# OSSIEPS.net
KiCad netlist of a schematic drawn in EAGLE
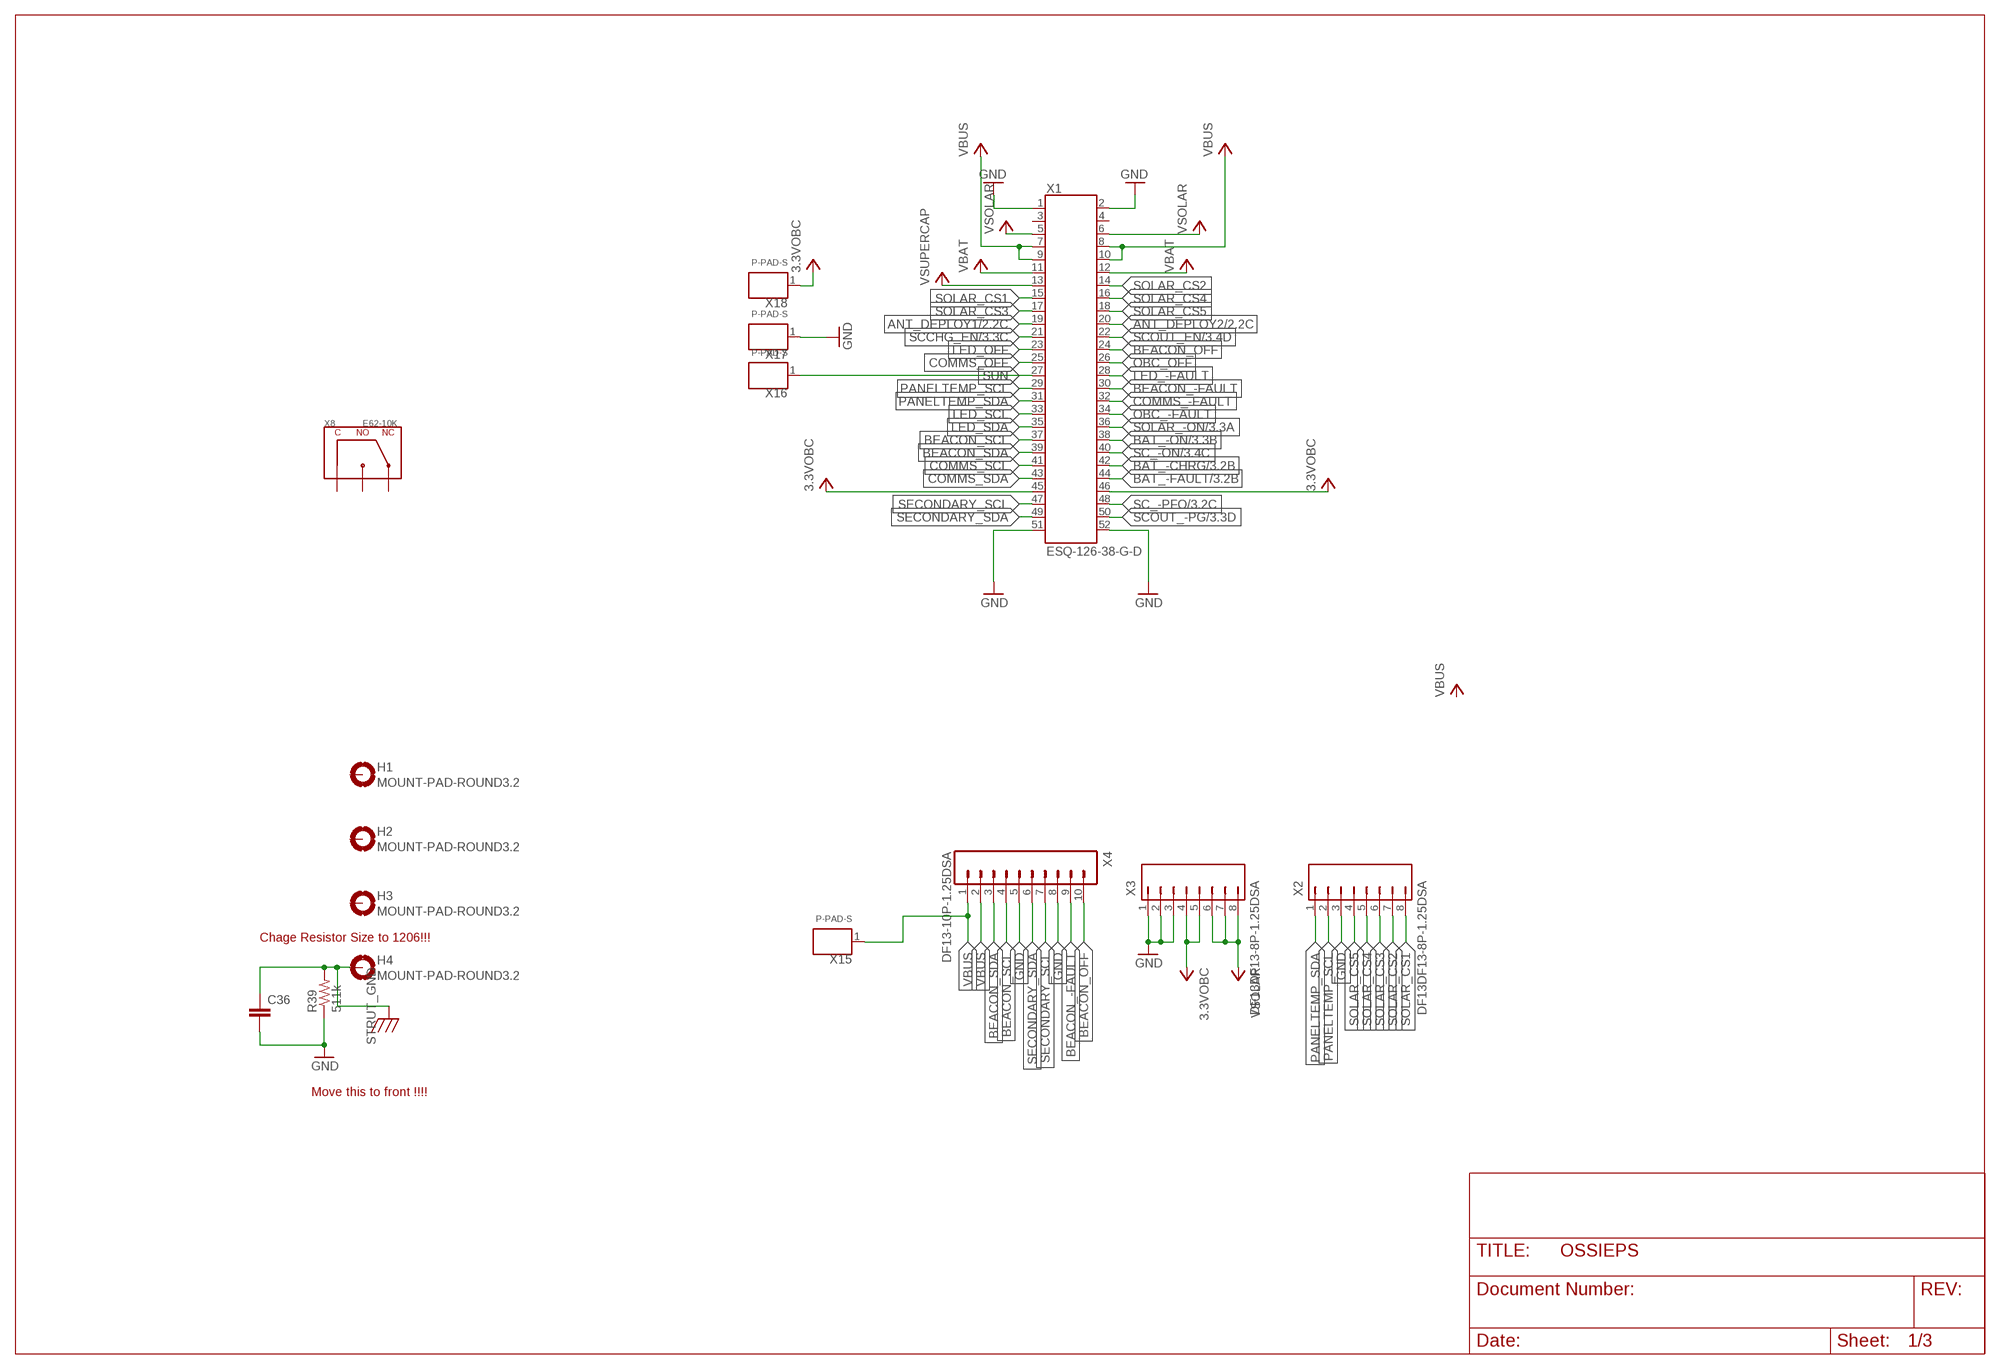
[diagram p0: schematic, sheet 1]
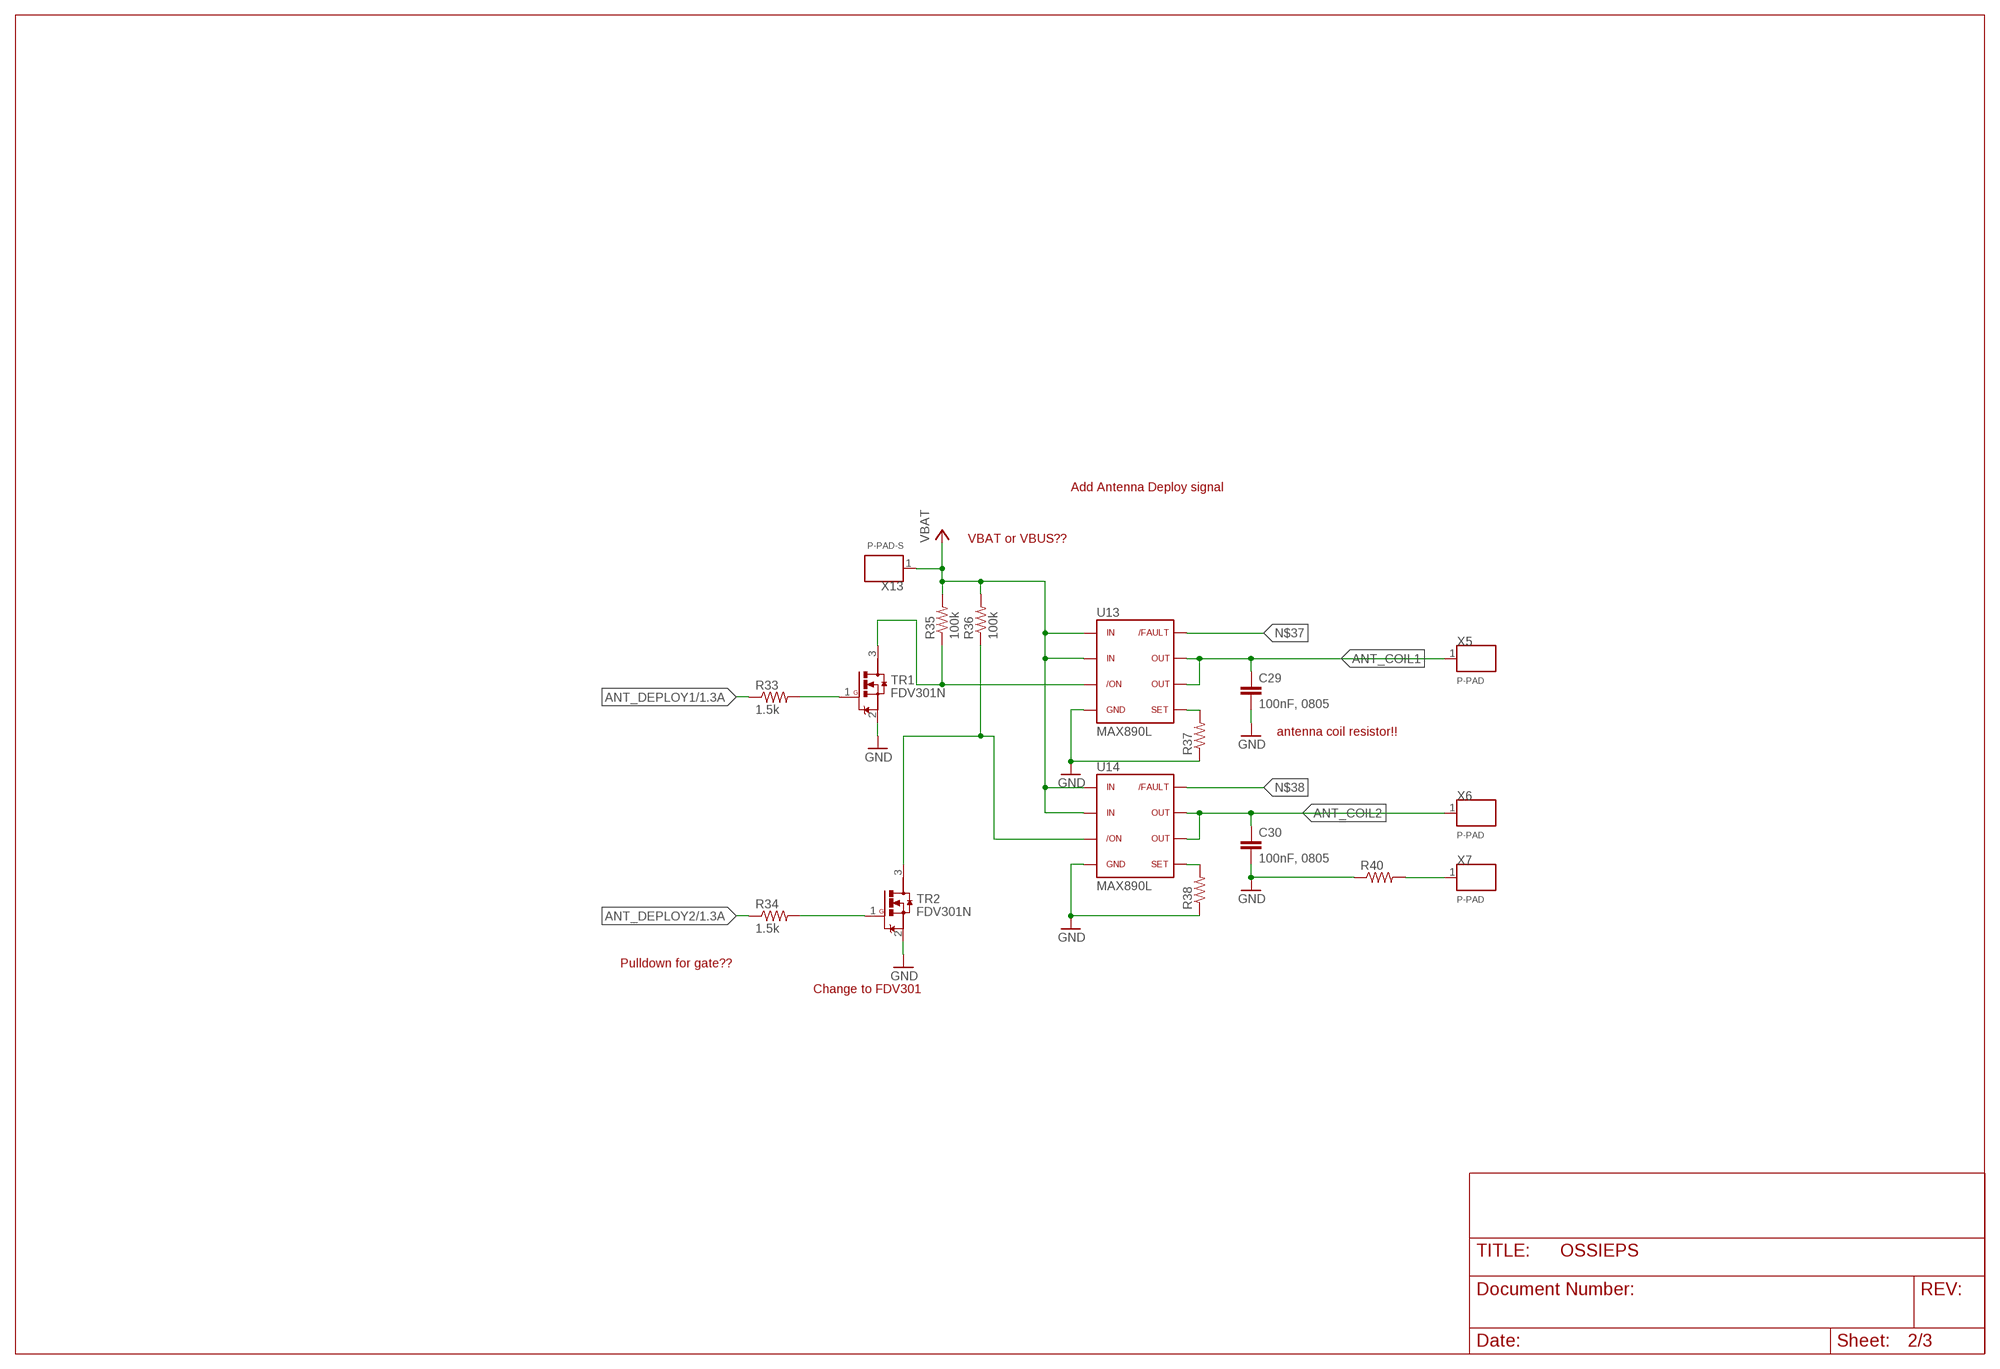
[diagram p1: schematic, sheet 2]
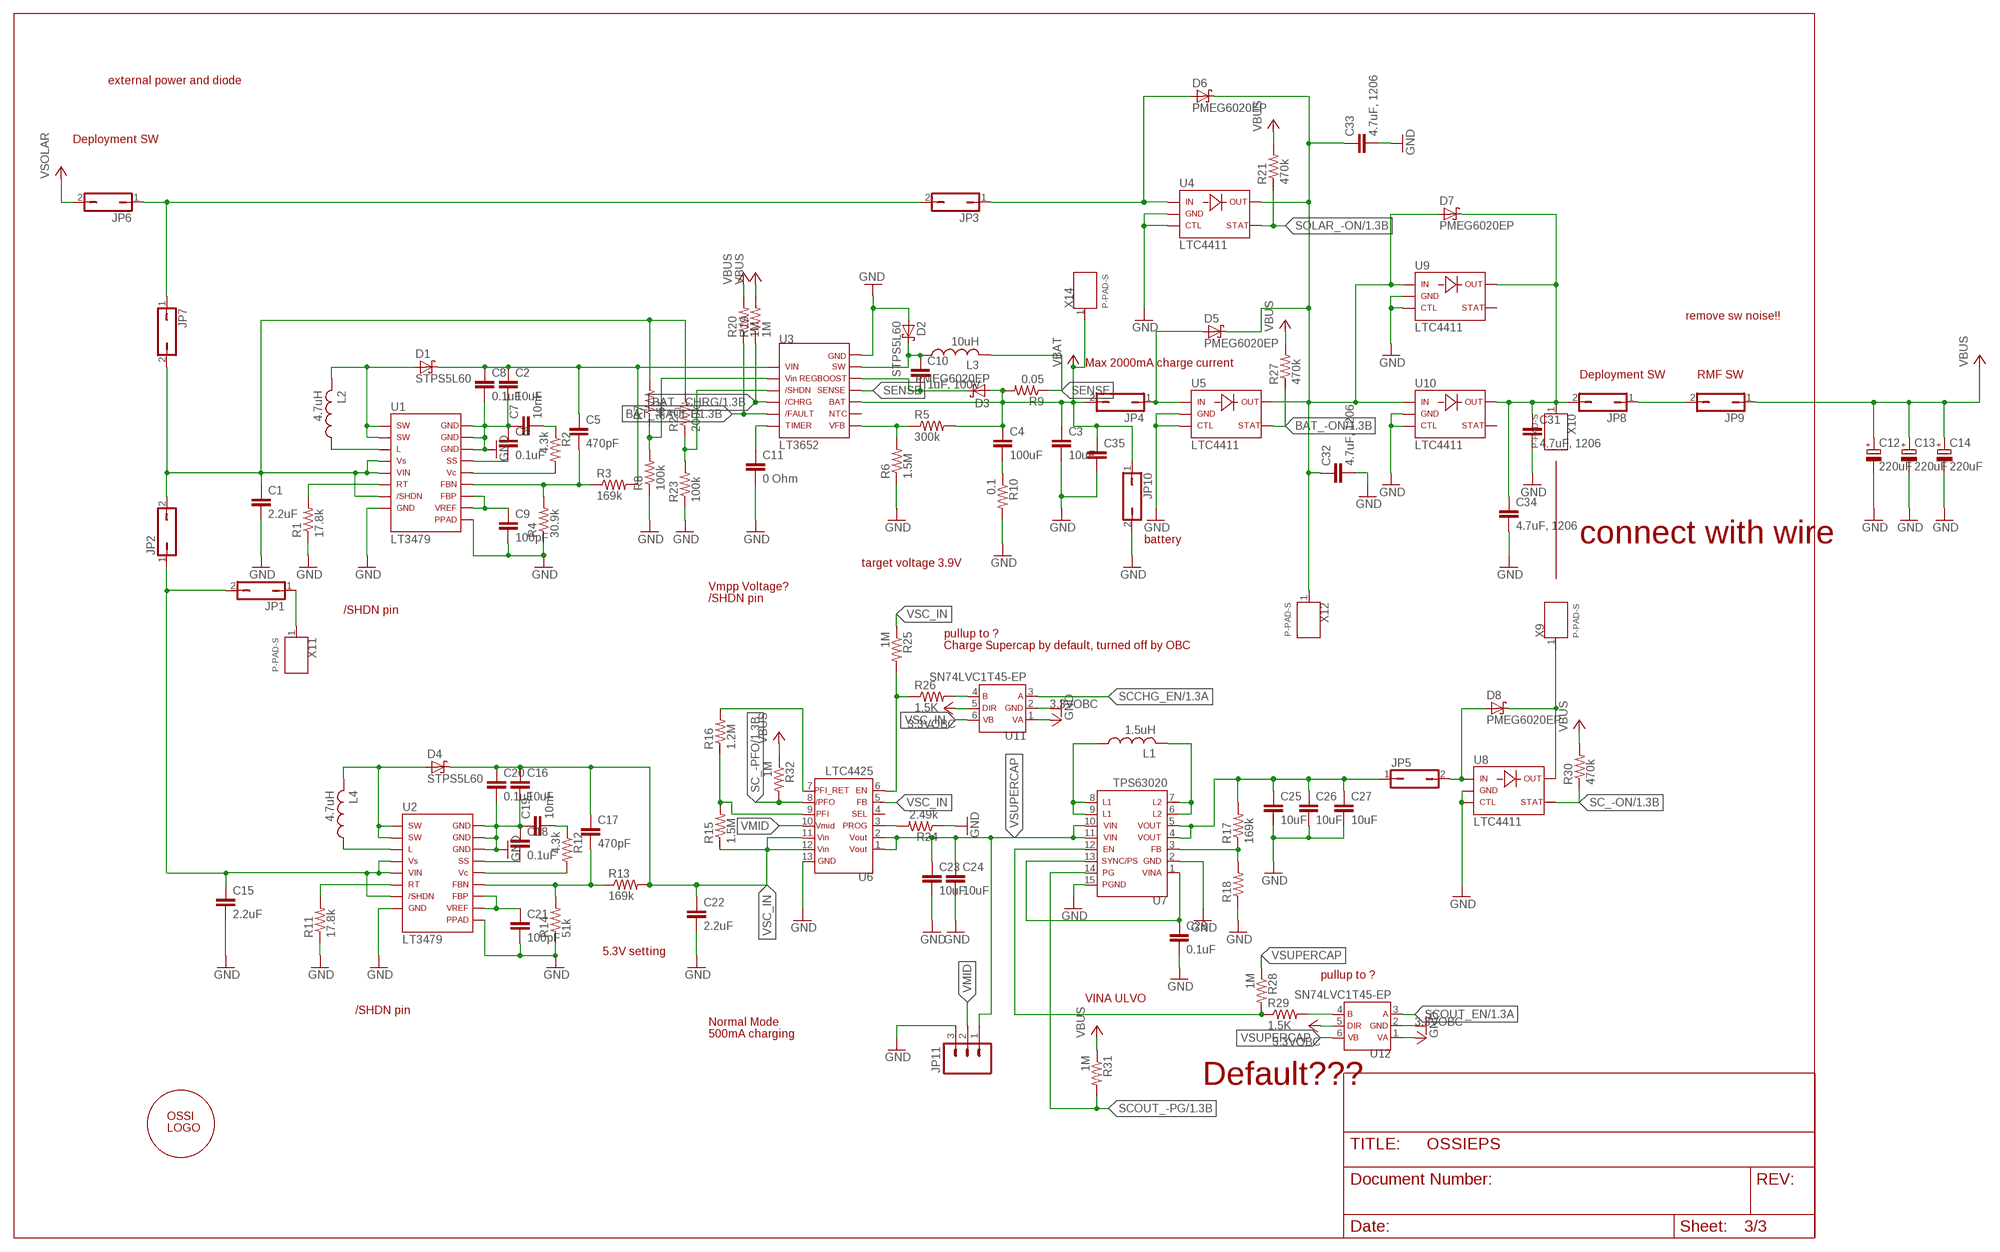
[diagram p2: schematic, sheet 3]

(export (version "E")
  (design (tool "Eeschema 10.0.6"))
  (components
    (comp (ref "C29")
      (value "100nF, 0805")
      (footprint "eagle-import:C0805(2012)")
      (libsource (lib "eagle-import") (part "C0805(2012)"))
    )
    (comp (ref "C30")
      (value "100nF, 0805")
      (footprint "eagle-import:C0805(2012)")
      (libsource (lib "eagle-import") (part "C0805(2012)"))
    )
    (comp (ref "R33")
      (value "1.5k")
      (footprint "eagle-import:R0603(1608)")
      (libsource (lib "eagle-import") (part "R0603(1608)"))
    )
    (comp (ref "R34")
      (value "1.5k")
      (footprint "eagle-import:R0603(1608)")
      (libsource (lib "eagle-import") (part "R0603(1608)"))
    )
    (comp (ref "R35")
      (value "100k")
      (footprint "eagle-import:R0603(1608)")
      (libsource (lib "eagle-import") (part "R0603(1608)"))
    )
    (comp (ref "R36")
      (value "100k")
      (footprint "eagle-import:R0603(1608)")
      (libsource (lib "eagle-import") (part "R0603(1608)"))
    )
    (comp (ref "R37")
      (value "R0603(1608)")
      (footprint "eagle-import:R0603(1608)")
      (libsource (lib "eagle-import") (part "R0603(1608)"))
    )
    (comp (ref "R38")
      (value "R0603(1608)")
      (footprint "eagle-import:R0603(1608)")
      (libsource (lib "eagle-import") (part "R0603(1608)"))
    )
    (comp (ref "R40")
      (value "RPWR263S")
      (footprint "eagle-import:PWR263S-20")
      (libsource (lib "eagle-import") (part "RPWR263S"))
    )
    (comp (ref "TR1")
      (value "FDV301N")
      (footprint "eagle-import:SOT23")
      (libsource (lib "eagle-import") (part "FDV301N"))
    )
    (comp (ref "TR2")
      (value "FDV301N")
      (footprint "eagle-import:SOT23")
      (libsource (lib "eagle-import") (part "FDV301N"))
    )
    (comp (ref "U13")
      (value "MAX890L")
      (footprint "eagle-import:SO8")
      (libsource (lib "eagle-import") (part "MAX890L"))
    )
    (comp (ref "U14")
      (value "MAX890L")
      (footprint "eagle-import:SO8")
      (libsource (lib "eagle-import") (part "MAX890L"))
    )
    (comp (ref "X5")
      (value "P-PAD")
      (footprint "eagle-import:P-PAD")
      (libsource (lib "eagle-import") (part "P-PAD"))
    )
    (comp (ref "X6")
      (value "P-PAD")
      (footprint "eagle-import:P-PAD")
      (libsource (lib "eagle-import") (part "P-PAD"))
    )
    (comp (ref "X7")
      (value "P-PAD")
      (footprint "eagle-import:P-PAD")
      (libsource (lib "eagle-import") (part "P-PAD"))
    )
    (comp (ref "X13")
      (value "P-PAD-S")
      (footprint "eagle-import:P-PAD-S")
      (libsource (lib "eagle-import") (part "P-PAD-S"))
    )
    (comp (ref "C1")
      (value "2.2uF")
      (footprint "eagle-import:C1206-GCM31")
      (libsource (lib "eagle-import") (part "C1206(3216)-GCM31"))
    )
    (comp (ref "C2")
      (value "10uF")
      (footprint "eagle-import:C1210-GCM32")
      (libsource (lib "eagle-import") (part "C1210(3225)-GCM32"))
    )
    (comp (ref "C3")
      (value "10uF")
      (footprint "eagle-import:C1210-GCM32")
      (libsource (lib "eagle-import") (part "C1210(3225)-GCM32"))
    )
    (comp (ref "C4")
      (value "100uF")
      (footprint "eagle-import:C1210-TMK325")
      (libsource (lib "eagle-import") (part "C1210(3225)-TMK325"))
    )
    (comp (ref "C5")
      (value "470pF")
      (footprint "eagle-import:C0603(1608)")
      (libsource (lib "eagle-import") (part "C0603(1608)"))
    )
    (comp (ref "C6")
      (value "0.1uF")
      (footprint "eagle-import:C0603(1608)")
      (libsource (lib "eagle-import") (part "C0603(1608)"))
    )
    (comp (ref "C7")
      (value "10nF")
      (footprint "eagle-import:C0603(1608)")
      (libsource (lib "eagle-import") (part "C0603(1608)"))
    )
    (comp (ref "C8")
      (value "0.1uF")
      (footprint "eagle-import:C0603(1608)")
      (libsource (lib "eagle-import") (part "C0603(1608)"))
    )
    (comp (ref "C9")
      (value "100pF")
      (footprint "eagle-import:C0603(1608)")
      (libsource (lib "eagle-import") (part "C0603(1608)"))
    )
    (comp (ref "C10")
      (value "1uF, 100V")
      (footprint "eagle-import:C0805(2012)")
      (libsource (lib "eagle-import") (part "C0805(2012)"))
    )
    (comp (ref "C11")
      (value "0 Ohm")
      (footprint "eagle-import:C0603(1608)")
      (libsource (lib "eagle-import") (part "C0603(1608)"))
    )
    (comp (ref "C12")
      (value "220uF")
      (footprint "eagle-import:C2917(7343)-Y")
      (libsource (lib "eagle-import") (part "C-TANTAL-Y"))
    )
    (comp (ref "C13")
      (value "220uF")
      (footprint "eagle-import:C2917(7343)-Y")
      (libsource (lib "eagle-import") (part "C-TANTAL-Y"))
    )
    (comp (ref "C14")
      (value "220uF")
      (footprint "eagle-import:C2917(7343)-Y")
      (libsource (lib "eagle-import") (part "C-TANTAL-Y"))
    )
    (comp (ref "C15")
      (value "2.2uF")
      (footprint "eagle-import:C1206-GCM31")
      (libsource (lib "eagle-import") (part "C1206(3216)-GCM31"))
    )
    (comp (ref "C16")
      (value "10uF")
      (footprint "eagle-import:C1210-GCM32")
      (libsource (lib "eagle-import") (part "C1210(3225)-GCM32"))
    )
    (comp (ref "C17")
      (value "470pF")
      (footprint "eagle-import:C0603(1608)")
      (libsource (lib "eagle-import") (part "C0603(1608)"))
    )
    (comp (ref "C18")
      (value "0.1uF")
      (footprint "eagle-import:C0603(1608)")
      (libsource (lib "eagle-import") (part "C0603(1608)"))
    )
    (comp (ref "C19")
      (value "10nF")
      (footprint "eagle-import:C0603(1608)")
      (libsource (lib "eagle-import") (part "C0603(1608)"))
    )
    (comp (ref "C20")
      (value "0.1uF")
      (footprint "eagle-import:C0603(1608)")
      (libsource (lib "eagle-import") (part "C0603(1608)"))
    )
    (comp (ref "C21")
      (value "100pF")
      (footprint "eagle-import:C0603(1608)")
      (libsource (lib "eagle-import") (part "C0603(1608)"))
    )
    (comp (ref "C22")
      (value "2.2uF")
      (footprint "eagle-import:C1206-GCM31")
      (libsource (lib "eagle-import") (part "C1206(3216)-GCM31"))
    )
    (comp (ref "C23")
      (value "10uF")
      (footprint "eagle-import:C1210-GCM32")
      (libsource (lib "eagle-import") (part "C1210(3225)-GCM32"))
    )
    (comp (ref "C24")
      (value "10uF")
      (footprint "eagle-import:C1210-GCM32")
      (libsource (lib "eagle-import") (part "C1210(3225)-GCM32"))
    )
    (comp (ref "C25")
      (value "10uF")
      (footprint "eagle-import:C1210-GCM32")
      (libsource (lib "eagle-import") (part "C1210(3225)-GCM32"))
    )
    (comp (ref "C26")
      (value "10uF")
      (footprint "eagle-import:C1210-GCM32")
      (libsource (lib "eagle-import") (part "C1210(3225)-GCM32"))
    )
    (comp (ref "C27")
      (value "10uF")
      (footprint "eagle-import:C1210-GCM32")
      (libsource (lib "eagle-import") (part "C1210(3225)-GCM32"))
    )
    (comp (ref "C28")
      (value "0.1uF")
      (footprint "eagle-import:C0603(1608)")
      (libsource (lib "eagle-import") (part "C0603(1608)"))
    )
    (comp (ref "C31")
      (value "4.7uF, 1206")
      (footprint "eagle-import:C1206-GCM31")
      (libsource (lib "eagle-import") (part "C1206(3216)-GCM31"))
    )
    (comp (ref "C32")
      (value "4.7uF, 1206")
      (footprint "eagle-import:C1206-GCM31")
      (libsource (lib "eagle-import") (part "C1206(3216)-GCM31"))
    )
    (comp (ref "C33")
      (value "4.7uF, 1206")
      (footprint "eagle-import:C1206-GCM31")
      (libsource (lib "eagle-import") (part "C1206(3216)-GCM31"))
    )
    (comp (ref "C34")
      (value "4.7uF, 1206")
      (footprint "eagle-import:C1206-GCM31")
      (libsource (lib "eagle-import") (part "C1206(3216)-GCM31"))
    )
    (comp (ref "C35")
      (value "C0603(1608)")
      (footprint "eagle-import:C0603(1608)")
      (libsource (lib "eagle-import") (part "C0603(1608)"))
    )
    (comp (ref "D1")
      (value "STPS5L60")
      (footprint "eagle-import:STPS5L60")
      (libsource (lib "eagle-import") (part "STPS5L60"))
    )
    (comp (ref "D2")
      (value "STPS5L60")
      (footprint "eagle-import:STPS5L60")
      (libsource (lib "eagle-import") (part "STPS5L60"))
    )
    (comp (ref "D3")
      (value "PMEG6020EP")
      (footprint "eagle-import:PMEG6020EP")
      (libsource (lib "eagle-import") (part "PMEG6020EP"))
    )
    (comp (ref "D4")
      (value "STPS5L60")
      (footprint "eagle-import:STPS5L60")
      (libsource (lib "eagle-import") (part "STPS5L60"))
    )
    (comp (ref "D5")
      (value "PMEG6020EP")
      (footprint "eagle-import:PMEG6020EP")
      (libsource (lib "eagle-import") (part "PMEG6020EP"))
    )
    (comp (ref "D6")
      (value "PMEG6020EP")
      (footprint "eagle-import:PMEG6020EP")
      (libsource (lib "eagle-import") (part "PMEG6020EP"))
    )
    (comp (ref "D7")
      (value "PMEG6020EP")
      (footprint "eagle-import:PMEG6020EP")
      (libsource (lib "eagle-import") (part "PMEG6020EP"))
    )
    (comp (ref "D8")
      (value "PMEG6020EP")
      (footprint "eagle-import:PMEG6020EP")
      (libsource (lib "eagle-import") (part "PMEG6020EP"))
    )
    (comp (ref "JP1")
      (value "JP1Q")
      (footprint "eagle-import:JP1")
      (libsource (lib "eagle-import") (part "JP1Q"))
    )
    (comp (ref "JP2")
      (value "JP1Q")
      (footprint "eagle-import:JP1")
      (libsource (lib "eagle-import") (part "JP1Q"))
    )
    (comp (ref "JP3")
      (value "JP1Q")
      (footprint "eagle-import:JP1")
      (libsource (lib "eagle-import") (part "JP1Q"))
    )
    (comp (ref "JP4")
      (value "JP1Q")
      (footprint "eagle-import:JP1")
      (libsource (lib "eagle-import") (part "JP1Q"))
    )
    (comp (ref "JP5")
      (value "JP1Q")
      (footprint "eagle-import:JP1")
      (libsource (lib "eagle-import") (part "JP1Q"))
    )
    (comp (ref "JP6")
      (value "JP1Q")
      (footprint "eagle-import:JP1")
      (libsource (lib "eagle-import") (part "JP1Q"))
    )
    (comp (ref "JP7")
      (value "JP1Q")
      (footprint "eagle-import:JP1")
      (libsource (lib "eagle-import") (part "JP1Q"))
    )
    (comp (ref "JP8")
      (value "JP1Q")
      (footprint "eagle-import:JP1")
      (libsource (lib "eagle-import") (part "JP1Q"))
    )
    (comp (ref "JP9")
      (value "JP1Q")
      (footprint "eagle-import:JP1")
      (libsource (lib "eagle-import") (part "JP1Q"))
    )
    (comp (ref "JP10")
      (value "JP1Q")
      (footprint "eagle-import:JP1")
      (libsource (lib "eagle-import") (part "JP1Q"))
    )
    (comp (ref "JP11")
      (value "M03POLAR")
      (footprint "eagle-import:MOLEX-1X3")
      (libsource (lib "eagle-import") (part "M03POLAR"))
    )
    (comp (ref "L1")
      (value "1.5uH")
      (footprint "eagle-import:L(4040)")
      (libsource (lib "eagle-import") (part "LXFL4020"))
    )
    (comp (ref "L2")
      (value "4.7uH")
      (footprint "eagle-import:RLF7030")
      (libsource (lib "eagle-import") (part "LRLF7030"))
    )
    (comp (ref "L3")
      (value "10uH")
      (footprint "eagle-import:RLF12545")
      (libsource (lib "eagle-import") (part "LRLF12545"))
    )
    (comp (ref "L4")
      (value "4.7uH")
      (footprint "eagle-import:RLF7030")
      (libsource (lib "eagle-import") (part "LRLF7030"))
    )
    (comp (ref "R1")
      (value "17.8k")
      (footprint "eagle-import:R0603(1608)")
      (libsource (lib "eagle-import") (part "R0603(1608)"))
    )
    (comp (ref "R2")
      (value "4.3k")
      (footprint "eagle-import:R0603(1608)")
      (libsource (lib "eagle-import") (part "R0603(1608)"))
    )
    (comp (ref "R3")
      (value "169k")
      (footprint "eagle-import:R0603(1608)")
      (libsource (lib "eagle-import") (part "R0603(1608)"))
    )
    (comp (ref "R4")
      (value "30.9k")
      (footprint "eagle-import:R0603(1608)")
      (libsource (lib "eagle-import") (part "R0603(1608)"))
    )
    (comp (ref "R5")
      (value "300k")
      (footprint "eagle-import:R0603(1608)")
      (libsource (lib "eagle-import") (part "R0603(1608)"))
    )
    (comp (ref "R6")
      (value "1.5M")
      (footprint "eagle-import:R0603(1608)")
      (libsource (lib "eagle-import") (part "R0603(1608)"))
    )
    (comp (ref "R7")
      (value "36k")
      (footprint "eagle-import:R0603(1608)")
      (libsource (lib "eagle-import") (part "R0603(1608)"))
    )
    (comp (ref "R8")
      (value "100k")
      (footprint "eagle-import:R0603(1608)")
      (libsource (lib "eagle-import") (part "R0603(1608)"))
    )
    (comp (ref "R9")
      (value "0.05")
      (footprint "eagle-import:WSL1206")
      (libsource (lib "eagle-import") (part "RWSL1206"))
    )
    (comp (ref "R10")
      (value "0.1")
      (footprint "eagle-import:WSL1206")
      (libsource (lib "eagle-import") (part "RWSL1206"))
    )
    (comp (ref "R11")
      (value "17.8k")
      (footprint "eagle-import:R0603(1608)")
      (libsource (lib "eagle-import") (part "R0603(1608)"))
    )
    (comp (ref "R12")
      (value "4.3k")
      (footprint "eagle-import:R0603(1608)")
      (libsource (lib "eagle-import") (part "R0603(1608)"))
    )
    (comp (ref "R13")
      (value "169k")
      (footprint "eagle-import:R0603(1608)")
      (libsource (lib "eagle-import") (part "R0603(1608)"))
    )
    (comp (ref "R14")
      (value "51k")
      (footprint "eagle-import:R0603(1608)")
      (libsource (lib "eagle-import") (part "R0603(1608)"))
    )
    (comp (ref "R15")
      (value "1.5M")
      (footprint "eagle-import:R0603(1608)")
      (libsource (lib "eagle-import") (part "R0603(1608)"))
    )
    (comp (ref "R16")
      (value "1.2M")
      (footprint "eagle-import:R0603(1608)")
      (libsource (lib "eagle-import") (part "R0603(1608)"))
    )
    (comp (ref "R17")
      (value "169k")
      (footprint "eagle-import:R0603(1608)")
      (libsource (lib "eagle-import") (part "R0603(1608)"))
    )
    (comp (ref "R18")
      (value "R0603(1608)")
      (footprint "eagle-import:R0603(1608)")
      (libsource (lib "eagle-import") (part "R0603(1608)"))
    )
    (comp (ref "R19")
      (value "1M")
      (footprint "eagle-import:R0603(1608)")
      (libsource (lib "eagle-import") (part "R0603(1608)"))
    )
    (comp (ref "R20")
      (value "1M")
      (footprint "eagle-import:R0603(1608)")
      (libsource (lib "eagle-import") (part "R0603(1608)"))
    )
    (comp (ref "R21")
      (value "470k")
      (footprint "eagle-import:R0603(1608)")
      (libsource (lib "eagle-import") (part "R0603(1608)"))
    )
    (comp (ref "R22")
      (value "200k")
      (footprint "eagle-import:R0603(1608)")
      (libsource (lib "eagle-import") (part "R0603(1608)"))
    )
    (comp (ref "R23")
      (value "100k")
      (footprint "eagle-import:R0603(1608)")
      (libsource (lib "eagle-import") (part "R0603(1608)"))
    )
    (comp (ref "R24")
      (value "2.49k")
      (footprint "eagle-import:R0603(1608)")
      (libsource (lib "eagle-import") (part "R0603(1608)"))
    )
    (comp (ref "R25")
      (value "1M")
      (footprint "eagle-import:R0603(1608)")
      (libsource (lib "eagle-import") (part "R0603(1608)"))
    )
    (comp (ref "R26")
      (value "1.5K")
      (footprint "eagle-import:R0603(1608)")
      (libsource (lib "eagle-import") (part "R0603(1608)"))
    )
    (comp (ref "R27")
      (value "470k")
      (footprint "eagle-import:R0603(1608)")
      (libsource (lib "eagle-import") (part "R0603(1608)"))
    )
    (comp (ref "R28")
      (value "1M")
      (footprint "eagle-import:R0603(1608)")
      (libsource (lib "eagle-import") (part "R0603(1608)"))
    )
    (comp (ref "R29")
      (value "1.5K")
      (footprint "eagle-import:R0603(1608)")
      (libsource (lib "eagle-import") (part "R0603(1608)"))
    )
    (comp (ref "R30")
      (value "470k")
      (footprint "eagle-import:R0603(1608)")
      (libsource (lib "eagle-import") (part "R0603(1608)"))
    )
    (comp (ref "R31")
      (value "1M")
      (footprint "eagle-import:R0603(1608)")
      (libsource (lib "eagle-import") (part "R0603(1608)"))
    )
    (comp (ref "R32")
      (value "1M")
      (footprint "eagle-import:R0603(1608)")
      (libsource (lib "eagle-import") (part "R0603(1608)"))
    )
    (comp (ref "U$1")
      (value "OSSILOGORECT")
      (footprint "eagle-import:OSSILOGORECT1005")
      (libsource (lib "eagle-import") (part "OSSILOGORECT"))
    )
    (comp (ref "U1")
      (value "LT3479")
      (footprint "eagle-import:TSSOP16-FE")
      (libsource (lib "eagle-import") (part "LT3479"))
    )
    (comp (ref "U2")
      (value "LT3479")
      (footprint "eagle-import:TSSOP16-FE")
      (libsource (lib "eagle-import") (part "LT3479"))
    )
    (comp (ref "U3")
      (value "LT3652")
      (footprint "eagle-import:MSE")
      (libsource (lib "eagle-import") (part "LT3652"))
    )
    (comp (ref "U4")
      (value "LTC4411")
      (footprint "eagle-import:TSOT23-5")
      (libsource (lib "eagle-import") (part "LTC4411"))
    )
    (comp (ref "U5")
      (value "LTC4411")
      (footprint "eagle-import:TSOT23-5")
      (libsource (lib "eagle-import") (part "LTC4411"))
    )
    (comp (ref "U6")
      (value "LTC4425")
      (footprint "eagle-import:MSE")
      (libsource (lib "eagle-import") (part "LTC4425"))
    )
    (comp (ref "U7")
      (value "TPS63020")
      (footprint "eagle-import:VSON-14")
      (libsource (lib "eagle-import") (part "TPS63020"))
    )
    (comp (ref "U8")
      (value "LTC4411")
      (footprint "eagle-import:TSOT23-5")
      (libsource (lib "eagle-import") (part "LTC4411"))
    )
    (comp (ref "U9")
      (value "LTC4411")
      (footprint "eagle-import:TSOT23-5")
      (libsource (lib "eagle-import") (part "LTC4411"))
    )
    (comp (ref "U10")
      (value "LTC4411")
      (footprint "eagle-import:TSOT23-5")
      (libsource (lib "eagle-import") (part "LTC4411"))
    )
    (comp (ref "U11")
      (value "SN74LVC1T45-EP")
      (footprint "eagle-import:SOT-6DCK")
      (libsource (lib "eagle-import") (part "SN74LVC1T45-EP"))
    )
    (comp (ref "U12")
      (value "SN74LVC1T45-EP")
      (footprint "eagle-import:SOT-6DCK")
      (libsource (lib "eagle-import") (part "SN74LVC1T45-EP"))
    )
    (comp (ref "X9")
      (value "P-PAD-S")
      (footprint "eagle-import:P-PAD-S")
      (libsource (lib "eagle-import") (part "P-PAD-S"))
    )
    (comp (ref "X10")
      (value "P-PAD-S")
      (footprint "eagle-import:P-PAD-S")
      (libsource (lib "eagle-import") (part "P-PAD-S"))
    )
    (comp (ref "X11")
      (value "P-PAD-S")
      (footprint "eagle-import:P-PAD-S")
      (libsource (lib "eagle-import") (part "P-PAD-S"))
    )
    (comp (ref "X12")
      (value "P-PAD-S")
      (footprint "eagle-import:P-PAD-S")
      (libsource (lib "eagle-import") (part "P-PAD-S"))
    )
    (comp (ref "X14")
      (value "P-PAD-S")
      (footprint "eagle-import:P-PAD-S")
      (libsource (lib "eagle-import") (part "P-PAD-S"))
    )
    (comp (ref "C36")
      (value "C0805(2012)")
      (footprint "eagle-import:C0805(2012)")
      (libsource (lib "eagle-import") (part "C0805(2012)"))
    )
    (comp (ref "H1")
      (value "MOUNT-PAD-ROUND3.2")
      (footprint "eagle-import:3.2-PAD-ROUND")
      (libsource (lib "eagle-import") (part "MOUNT-PAD-ROUND3.2"))
    )
    (comp (ref "H2")
      (value "MOUNT-PAD-ROUND3.2")
      (footprint "eagle-import:3.2-PAD-ROUND")
      (libsource (lib "eagle-import") (part "MOUNT-PAD-ROUND3.2"))
    )
    (comp (ref "H3")
      (value "MOUNT-PAD-ROUND3.2")
      (footprint "eagle-import:3.2-PAD-ROUND")
      (libsource (lib "eagle-import") (part "MOUNT-PAD-ROUND3.2"))
    )
    (comp (ref "H4")
      (value "MOUNT-PAD-ROUND3.2")
      (footprint "eagle-import:3.2-PAD-ROUND")
      (libsource (lib "eagle-import") (part "MOUNT-PAD-ROUND3.2"))
    )
    (comp (ref "R39")
      (value "511k")
      (footprint "eagle-import:R0805(2012)")
      (libsource (lib "eagle-import") (part "R0805(2012)"))
    )
    (comp (ref "X1")
      (value "ESQ-126-38-G-D")
      (footprint "eagle-import:ESQ-126-XX-X-D")
      (libsource (lib "eagle-import") (part "ESQ-126-38-G-D"))
    )
    (comp (ref "X2")
      (value "DF13DF13-8P-1.25DSA")
      (footprint "eagle-import:DF13-8P-1.25DSA")
      (libsource (lib "eagle-import") (part "DF13DF13-8P-1.25DSA"))
    )
    (comp (ref "X3")
      (value "DF13DF13-8P-1.25DSA")
      (footprint "eagle-import:DF13-8P-1.25DSA")
      (libsource (lib "eagle-import") (part "DF13DF13-8P-1.25DSA"))
    )
    (comp (ref "X4")
      (value "DF13-10P-1.25DSA")
      (footprint "eagle-import:DF13-10P-1.25DSA")
      (libsource (lib "eagle-import") (part "DF13-10P-1.25DSA"))
    )
    (comp (ref "X8")
      (value "E62-10K")
      (footprint "eagle-import:E62-10K")
      (libsource (lib "eagle-import") (part "E62-10K"))
    )
    (comp (ref "X15")
      (value "P-PAD-S")
      (footprint "eagle-import:P-PAD-S")
      (libsource (lib "eagle-import") (part "P-PAD-S"))
    )
    (comp (ref "X16")
      (value "P-PAD-S")
      (footprint "eagle-import:P-PAD-S")
      (libsource (lib "eagle-import") (part "P-PAD-S"))
    )
    (comp (ref "X17")
      (value "P-PAD-S")
      (footprint "eagle-import:P-PAD-S")
      (libsource (lib "eagle-import") (part "P-PAD-S"))
    )
    (comp (ref "X18")
      (value "P-PAD-S")
      (footprint "eagle-import:P-PAD-S")
      (libsource (lib "eagle-import") (part "P-PAD-S"))
    )
  )
  (nets
    (net (code "1") (name "3.3VOBC") (class "Default")
      (node (ref "U11") (pin "1") (pinfunction "P$1_1") (pintype "bidirectional"))
      (node (ref "U11") (pin "5") (pinfunction "P$5_5") (pintype "bidirectional"))
      (node (ref "U12") (pin "1") (pinfunction "P$1_1") (pintype "bidirectional"))
      (node (ref "U12") (pin "5") (pinfunction "P$5_5") (pintype "bidirectional"))
      (node (ref "X1") (pin "45") (pinfunction "45_45") (pintype "bidirectional"))
      (node (ref "X1") (pin "46") (pinfunction "46_46") (pintype "bidirectional"))
      (node (ref "X18") (pin "1") (pinfunction "P$1_1") (pintype "bidirectional"))
      (node (ref "X3") (pin "4") (pinfunction "4_4") (pintype "passive"))
      (node (ref "X3") (pin "5") (pinfunction "5_5") (pintype "passive"))
    )
    (net (code "2") (name "ANT_COIL1") (class "Default")
      (node (ref "C29") (pin "1") (pinfunction "1_1") (pintype "passive"))
      (node (ref "U13") (pin "6") (pinfunction "P$6_6") (pintype "output"))
      (node (ref "U13") (pin "7") (pinfunction "P$7_7") (pintype "output"))
      (node (ref "X5") (pin "1") (pinfunction "P$1_1") (pintype "bidirectional"))
    )
    (net (code "3") (name "ANT_COIL2") (class "Default")
      (node (ref "C30") (pin "1") (pinfunction "1_1") (pintype "passive"))
      (node (ref "U14") (pin "6") (pinfunction "P$6_6") (pintype "output"))
      (node (ref "U14") (pin "7") (pinfunction "P$7_7") (pintype "output"))
      (node (ref "X6") (pin "1") (pinfunction "P$1_1") (pintype "bidirectional"))
    )
    (net (code "4") (name "ANT_DEPLOY1") (class "Default")
      (node (ref "R33") (pin "1") (pinfunction "1_1") (pintype "passive"))
      (node (ref "X1") (pin "19") (pinfunction "19_19") (pintype "bidirectional"))
    )
    (net (code "5") (name "ANT_DEPLOY2") (class "Default")
      (node (ref "R34") (pin "1") (pinfunction "1_1") (pintype "passive"))
      (node (ref "X1") (pin "20") (pinfunction "20_20") (pintype "bidirectional"))
    )
    (net (code "6") (name "BAT_-CHRG") (class "Default")
      (node (ref "R19") (pin "1") (pinfunction "1_1") (pintype "passive"))
      (node (ref "U3") (pin "4") (pinfunction "P$4_4") (pintype "output"))
      (node (ref "X1") (pin "42") (pinfunction "42_42") (pintype "bidirectional"))
    )
    (net (code "7") (name "BAT_-FAULT") (class "Default")
      (node (ref "R20") (pin "1") (pinfunction "1_1") (pintype "passive"))
      (node (ref "U3") (pin "5") (pinfunction "P$5_5") (pintype "output"))
      (node (ref "X1") (pin "44") (pinfunction "44_44") (pintype "bidirectional"))
    )
    (net (code "8") (name "BAT_-ON") (class "Default")
      (node (ref "R27") (pin "1") (pinfunction "1_1") (pintype "passive"))
      (node (ref "U5") (pin "P$4") (pinfunction "P$4_P$4") (pintype "output"))
      (node (ref "X1") (pin "38") (pinfunction "38_38") (pintype "bidirectional"))
    )
    (net (code "9") (name "BEACON_-FAULT") (class "Default")
      (node (ref "X1") (pin "30") (pinfunction "30_30") (pintype "bidirectional"))
      (node (ref "X4") (pin "9") (pinfunction "9_9") (pintype "passive"))
    )
    (net (code "10") (name "BEACON_OFF") (class "Default")
      (node (ref "X1") (pin "24") (pinfunction "24_24") (pintype "bidirectional"))
      (node (ref "X4") (pin "10") (pinfunction "10_10") (pintype "passive"))
    )
    (net (code "11") (name "BEACON_SCL") (class "Default")
      (node (ref "X1") (pin "37") (pinfunction "37_37") (pintype "bidirectional"))
      (node (ref "X4") (pin "4") (pinfunction "4_4") (pintype "passive"))
    )
    (net (code "12") (name "BEACON_SDA") (class "Default")
      (node (ref "X1") (pin "39") (pinfunction "39_39") (pintype "bidirectional"))
      (node (ref "X4") (pin "3") (pinfunction "3_3") (pintype "passive"))
    )
    (net (code "13") (name "COMMS_-FAULT") (class "Default")
      (node (ref "X1") (pin "32") (pinfunction "32_32") (pintype "bidirectional"))
    )
    (net (code "14") (name "COMMS_OFF") (class "Default")
      (node (ref "X1") (pin "25") (pinfunction "25_25") (pintype "bidirectional"))
    )
    (net (code "15") (name "COMMS_SCL") (class "Default")
      (node (ref "X1") (pin "41") (pinfunction "41_41") (pintype "bidirectional"))
    )
    (net (code "16") (name "COMMS_SDA") (class "Default")
      (node (ref "X1") (pin "43") (pinfunction "43_43") (pintype "bidirectional"))
    )
    (net (code "17") (name "GND") (class "Default")
      (node (ref "C1") (pin "P$2") (pinfunction "2_P$2") (pintype "passive"))
      (node (ref "C11") (pin "2") (pinfunction "2_2") (pintype "passive"))
      (node (ref "C12") (pin "2") (pinfunction "-_2") (pintype "passive"))
      (node (ref "C13") (pin "2") (pinfunction "-_2") (pintype "passive"))
      (node (ref "C14") (pin "2") (pinfunction "-_2") (pintype "passive"))
      (node (ref "C15") (pin "P$2") (pinfunction "2_P$2") (pintype "passive"))
      (node (ref "C16") (pin "P$2") (pinfunction "2_P$2") (pintype "passive"))
      (node (ref "C18") (pin "1") (pinfunction "1_1") (pintype "passive"))
      (node (ref "C19") (pin "1") (pinfunction "1_1") (pintype "passive"))
      (node (ref "C2") (pin "P$2") (pinfunction "2_P$2") (pintype "passive"))
      (node (ref "C20") (pin "2") (pinfunction "2_2") (pintype "passive"))
      (node (ref "C21") (pin "2") (pinfunction "2_2") (pintype "passive"))
      (node (ref "C22") (pin "P$2") (pinfunction "2_P$2") (pintype "passive"))
      (node (ref "C23") (pin "P$2") (pinfunction "2_P$2") (pintype "passive"))
      (node (ref "C24") (pin "P$2") (pinfunction "2_P$2") (pintype "passive"))
      (node (ref "C25") (pin "P$2") (pinfunction "2_P$2") (pintype "passive"))
      (node (ref "C26") (pin "P$2") (pinfunction "2_P$2") (pintype "passive"))
      (node (ref "C27") (pin "P$2") (pinfunction "2_P$2") (pintype "passive"))
      (node (ref "C28") (pin "2") (pinfunction "2_2") (pintype "passive"))
      (node (ref "C29") (pin "2") (pinfunction "2_2") (pintype "passive"))
      (node (ref "C3") (pin "P$2") (pinfunction "2_P$2") (pintype "passive"))
      (node (ref "C30") (pin "2") (pinfunction "2_2") (pintype "passive"))
      (node (ref "C31") (pin "P$2") (pinfunction "2_P$2") (pintype "passive"))
      (node (ref "C32") (pin "P$2") (pinfunction "2_P$2") (pintype "passive"))
      (node (ref "C33") (pin "P$2") (pinfunction "2_P$2") (pintype "passive"))
      (node (ref "C34") (pin "P$2") (pinfunction "2_P$2") (pintype "passive"))
      (node (ref "C35") (pin "2") (pinfunction "2_2") (pintype "passive"))
      (node (ref "C36") (pin "2") (pinfunction "2_2") (pintype "passive"))
      (node (ref "C6") (pin "1") (pinfunction "1_1") (pintype "passive"))
      (node (ref "C7") (pin "1") (pinfunction "1_1") (pintype "passive"))
      (node (ref "C8") (pin "2") (pinfunction "2_2") (pintype "passive"))
      (node (ref "C9") (pin "2") (pinfunction "2_2") (pintype "passive"))
      (node (ref "D2") (pin "A") (pinfunction "A_A") (pintype "passive"))
      (node (ref "JP10") (pin "2") (pinfunction "2_2") (pintype "passive"))
      (node (ref "JP11") (pin "3") (pinfunction "3_3") (pintype "passive"))
      (node (ref "R1") (pin "1") (pinfunction "1_1") (pintype "passive"))
      (node (ref "R10") (pin "P$2") (pinfunction "2_P$2") (pintype "passive"))
      (node (ref "R11") (pin "1") (pinfunction "1_1") (pintype "passive"))
      (node (ref "R14") (pin "1") (pinfunction "1_1") (pintype "passive"))
      (node (ref "R18") (pin "1") (pinfunction "1_1") (pintype "passive"))
      (node (ref "R23") (pin "1") (pinfunction "1_1") (pintype "passive"))
      (node (ref "R24") (pin "1") (pinfunction "1_1") (pintype "passive"))
      (node (ref "R37") (pin "1") (pinfunction "1_1") (pintype "passive"))
      (node (ref "R38") (pin "1") (pinfunction "1_1") (pintype "passive"))
      (node (ref "R39") (pin "1") (pinfunction "1_1") (pintype "passive"))
      (node (ref "R4") (pin "1") (pinfunction "1_1") (pintype "passive"))
      (node (ref "R40") (pin "P$1") (pinfunction "1_P$1") (pintype "passive"))
      (node (ref "R6") (pin "1") (pinfunction "1_1") (pintype "passive"))
      (node (ref "R8") (pin "1") (pinfunction "1_1") (pintype "passive"))
      (node (ref "TR1") (pin "2") (pinfunction "S_2") (pintype "bidirectional"))
      (node (ref "TR2") (pin "2") (pinfunction "S_2") (pintype "bidirectional"))
      (node (ref "U1") (pin "14") (pinfunction "P$14_14") (pintype "power_in"))
      (node (ref "U1") (pin "15") (pinfunction "P$15_15") (pintype "power_in"))
      (node (ref "U1") (pin "16") (pinfunction "P$16_16") (pintype "power_in"))
      (node (ref "U1") (pin "8") (pinfunction "P$8_8") (pintype "power_in"))
      (node (ref "U1") (pin "PPAD") (pinfunction "P$17_PPAD") (pintype "power_in"))
      (node (ref "U10") (pin "P$2") (pinfunction "P$2_P$2") (pintype "power_in"))
      (node (ref "U10") (pin "P$3") (pinfunction "P$3_P$3") (pintype "input"))
      (node (ref "U11") (pin "2") (pinfunction "P$2_2") (pintype "bidirectional"))
      (node (ref "U12") (pin "2") (pinfunction "P$2_2") (pintype "bidirectional"))
      (node (ref "U13") (pin "4") (pinfunction "P$4_4") (pintype "power_in"))
      (node (ref "U14") (pin "4") (pinfunction "P$4_4") (pintype "power_in"))
      (node (ref "U2") (pin "14") (pinfunction "P$14_14") (pintype "power_in"))
      (node (ref "U2") (pin "15") (pinfunction "P$15_15") (pintype "power_in"))
      (node (ref "U2") (pin "16") (pinfunction "P$16_16") (pintype "power_in"))
      (node (ref "U2") (pin "8") (pinfunction "P$8_8") (pintype "power_in"))
      (node (ref "U2") (pin "PPAD") (pinfunction "P$17_PPAD") (pintype "power_in"))
      (node (ref "U3") (pin "13") (pinfunction "P$13_13") (pintype "bidirectional"))
      (node (ref "U4") (pin "P$2") (pinfunction "P$2_P$2") (pintype "power_in"))
      (node (ref "U4") (pin "P$3") (pinfunction "P$3_P$3") (pintype "input"))
      (node (ref "U5") (pin "P$2") (pinfunction "P$2_P$2") (pintype "power_in"))
      (node (ref "U5") (pin "P$3") (pinfunction "P$3_P$3") (pintype "input"))
      (node (ref "U6") (pin "13") (pinfunction "P$13_13") (pintype "power_in"))
      (node (ref "U7") (pin "15") (pinfunction "PGND_15") (pintype "power_in"))
      (node (ref "U7") (pin "2") (pinfunction "GND_2") (pintype "power_in"))
      (node (ref "U8") (pin "P$2") (pinfunction "P$2_P$2") (pintype "power_in"))
      (node (ref "U8") (pin "P$3") (pinfunction "P$3_P$3") (pintype "input"))
      (node (ref "U9") (pin "P$2") (pinfunction "P$2_P$2") (pintype "power_in"))
      (node (ref "U9") (pin "P$3") (pinfunction "P$3_P$3") (pintype "input"))
      (node (ref "X1") (pin "1") (pinfunction "1_1") (pintype "bidirectional"))
      (node (ref "X1") (pin "2") (pinfunction "2_2") (pintype "bidirectional"))
      (node (ref "X1") (pin "51") (pinfunction "51_51") (pintype "bidirectional"))
      (node (ref "X1") (pin "52") (pinfunction "52_52") (pintype "bidirectional"))
      (node (ref "X17") (pin "1") (pinfunction "P$1_1") (pintype "bidirectional"))
      (node (ref "X2") (pin "3") (pinfunction "3_3") (pintype "passive"))
      (node (ref "X3") (pin "1") (pinfunction "1_1") (pintype "passive"))
      (node (ref "X3") (pin "2") (pinfunction "2_2") (pintype "passive"))
      (node (ref "X3") (pin "3") (pinfunction "3_3") (pintype "passive"))
      (node (ref "X4") (pin "5") (pinfunction "5_5") (pintype "passive"))
      (node (ref "X4") (pin "8") (pinfunction "8_8") (pintype "passive"))
    )
    (net (code "18") (name "LED_-FAULT") (class "Default")
      (node (ref "X1") (pin "28") (pinfunction "28_28") (pintype "bidirectional"))
    )
    (net (code "19") (name "LED_OFF") (class "Default")
      (node (ref "X1") (pin "23") (pinfunction "23_23") (pintype "bidirectional"))
    )
    (net (code "20") (name "LED_SCL") (class "Default")
      (node (ref "X1") (pin "33") (pinfunction "33_33") (pintype "bidirectional"))
    )
    (net (code "21") (name "LED_SDA") (class "Default")
      (node (ref "X1") (pin "35") (pinfunction "35_35") (pintype "bidirectional"))
    )
    (net (code "22") (name "N$37") (class "Default")
      (node (ref "U13") (pin "8") (pinfunction "P$8_8") (pintype "output"))
    )
    (net (code "23") (name "N$38") (class "Default")
      (node (ref "U14") (pin "8") (pinfunction "P$8_8") (pintype "output"))
    )
    (net (code "24") (name "Net-(C1-1)") (class "Default")
      (node (ref "C1") (pin "P$1") (pinfunction "1_P$1") (pintype "passive"))
      (node (ref "JP2") (pin "2") (pinfunction "2_2") (pintype "passive"))
      (node (ref "JP7") (pin "2") (pinfunction "2_2") (pintype "passive"))
      (node (ref "R22") (pin "2") (pinfunction "2_2") (pintype "passive"))
      (node (ref "R7") (pin "2") (pinfunction "2_2") (pintype "passive"))
      (node (ref "U1") (pin "4") (pinfunction "P$4_4") (pintype "power_in"))
      (node (ref "U1") (pin "5") (pinfunction "P$5_5") (pintype "power_in"))
      (node (ref "U1") (pin "7") (pinfunction "P$7_7") (pintype "input"))
    )
    (net (code "25") (name "Net-(C2-1)") (class "Default")
      (node (ref "C2") (pin "P$1") (pinfunction "1_P$1") (pintype "passive"))
      (node (ref "C5") (pin "1") (pinfunction "1_1") (pintype "passive"))
      (node (ref "C8") (pin "1") (pinfunction "1_1") (pintype "passive"))
      (node (ref "D1") (pin "C") (pinfunction "C_C") (pintype "passive"))
      (node (ref "R3") (pin "2") (pinfunction "2_2") (pintype "passive"))
      (node (ref "U3") (pin "1") (pinfunction "P$1_1") (pintype "power_in"))
    )
    (net (code "26") (name "Net-(C4-2)") (class "Default")
      (node (ref "C4") (pin "P$2") (pinfunction "2_P$2") (pintype "passive"))
      (node (ref "R10") (pin "P$1") (pinfunction "1_P$1") (pintype "passive"))
    )
    (net (code "27") (name "Net-(C7-Pad2)") (class "Default")
      (node (ref "C7") (pin "2") (pinfunction "2_2") (pintype "passive"))
      (node (ref "R2") (pin "1") (pinfunction "1_1") (pintype "passive"))
    )
    (net (code "28") (name "Net-(C15-1)") (class "Default")
      (node (ref "C15") (pin "P$1") (pinfunction "1_P$1") (pintype "passive"))
      (node (ref "JP1") (pin "2") (pinfunction "2_2") (pintype "passive"))
      (node (ref "JP2") (pin "1") (pinfunction "1_1") (pintype "passive"))
      (node (ref "U2") (pin "4") (pinfunction "P$4_4") (pintype "power_in"))
      (node (ref "U2") (pin "5") (pinfunction "P$5_5") (pintype "power_in"))
      (node (ref "U2") (pin "7") (pinfunction "P$7_7") (pintype "input"))
    )
    (net (code "29") (name "Net-(C19-Pad2)") (class "Default")
      (node (ref "C19") (pin "2") (pinfunction "2_2") (pintype "passive"))
      (node (ref "R12") (pin "1") (pinfunction "1_1") (pintype "passive"))
    )
    (net (code "30") (name "Net-(C25-1)") (class "Default")
      (node (ref "C25") (pin "P$1") (pinfunction "1_P$1") (pintype "passive"))
      (node (ref "C26") (pin "P$1") (pinfunction "1_P$1") (pintype "passive"))
      (node (ref "C27") (pin "P$1") (pinfunction "1_P$1") (pintype "passive"))
      (node (ref "JP5") (pin "1") (pinfunction "1_1") (pintype "passive"))
      (node (ref "R17") (pin "2") (pinfunction "2_2") (pintype "passive"))
      (node (ref "U7") (pin "4") (pinfunction "VOUT_4") (pintype "output"))
      (node (ref "U7") (pin "5") (pinfunction "VOUT2_5") (pintype "output"))
    )
    (net (code "31") (name "Net-(C31-1)") (class "Default")
      (node (ref "C31") (pin "P$1") (pinfunction "1_P$1") (pintype "passive"))
      (node (ref "C34") (pin "P$1") (pinfunction "1_P$1") (pintype "passive"))
      (node (ref "D7") (pin "C") (pinfunction "C_C") (pintype "passive"))
      (node (ref "JP8") (pin "2") (pinfunction "2_2") (pintype "passive"))
      (node (ref "U10") (pin "P$5") (pinfunction "P$5_P$5") (pintype "power_in"))
      (node (ref "U9") (pin "P$5") (pinfunction "P$5_P$5") (pintype "power_in"))
      (node (ref "X10") (pin "1") (pinfunction "P$1_1") (pintype "bidirectional"))
    )
    (net (code "32") (name "Net-(C32-1)") (class "Default")
      (node (ref "C32") (pin "P$1") (pinfunction "1_P$1") (pintype "passive"))
      (node (ref "C33") (pin "P$1") (pinfunction "1_P$1") (pintype "passive"))
      (node (ref "D5") (pin "C") (pinfunction "C_C") (pintype "passive"))
      (node (ref "D6") (pin "C") (pinfunction "C_C") (pintype "passive"))
      (node (ref "D7") (pin "A") (pinfunction "A_A") (pintype "passive"))
      (node (ref "U10") (pin "P$1") (pinfunction "P$1_P$1") (pintype "input"))
      (node (ref "U4") (pin "P$5") (pinfunction "P$5_P$5") (pintype "power_in"))
      (node (ref "U5") (pin "P$5") (pinfunction "P$5_P$5") (pintype "power_in"))
      (node (ref "U9") (pin "P$1") (pinfunction "P$1_P$1") (pintype "input"))
      (node (ref "X12") (pin "1") (pinfunction "P$1_1") (pintype "bidirectional"))
    )
    (net (code "33") (name "Net-(D5-PadA)") (class "Default")
      (node (ref "D5") (pin "A") (pinfunction "A_A") (pintype "passive"))
      (node (ref "JP4") (pin "1") (pinfunction "1_1") (pintype "passive"))
      (node (ref "U5") (pin "P$1") (pinfunction "P$1_P$1") (pintype "input"))
    )
    (net (code "34") (name "Net-(D6-PadA)") (class "Default")
      (node (ref "D6") (pin "A") (pinfunction "A_A") (pintype "passive"))
      (node (ref "JP3") (pin "1") (pinfunction "1_1") (pintype "passive"))
      (node (ref "U4") (pin "P$1") (pinfunction "P$1_P$1") (pintype "input"))
    )
    (net (code "35") (name "Net-(D8-PadA)") (class "Default")
      (node (ref "D8") (pin "A") (pinfunction "A_A") (pintype "passive"))
      (node (ref "JP5") (pin "2") (pinfunction "2_2") (pintype "passive"))
      (node (ref "U8") (pin "P$1") (pinfunction "P$1_P$1") (pintype "input"))
    )
    (net (code "36") (name "Net-(JP3-Pad2)") (class "Default")
      (node (ref "JP3") (pin "2") (pinfunction "2_2") (pintype "passive"))
      (node (ref "JP6") (pin "1") (pinfunction "1_1") (pintype "passive"))
      (node (ref "JP7") (pin "1") (pinfunction "1_1") (pintype "passive"))
    )
    (net (code "37") (name "Net-(JP8-Pad1)") (class "Default")
      (node (ref "JP8") (pin "1") (pinfunction "1_1") (pintype "passive"))
      (node (ref "JP9") (pin "2") (pinfunction "2_2") (pintype "passive"))
    )
    (net (code "38") (name "Net-(L2-1)") (class "Default")
      (node (ref "L2") (pin "P$1") (pinfunction "1_P$1") (pintype "passive"))
      (node (ref "U1") (pin "3") (pinfunction "P$3_3") (pintype "passive"))
    )
    (net (code "39") (name "Net-(L2-2)") (class "Default")
      (node (ref "D1") (pin "A") (pinfunction "A_A") (pintype "passive"))
      (node (ref "L2") (pin "P$2") (pinfunction "2_P$2") (pintype "passive"))
      (node (ref "U1") (pin "1") (pinfunction "P$1_1") (pintype "power_in"))
      (node (ref "U1") (pin "2") (pinfunction "P$2_2") (pintype "power_in"))
    )
    (net (code "40") (name "Net-(L3-1)") (class "Default")
      (node (ref "C10") (pin "1") (pinfunction "1_1") (pintype "passive"))
      (node (ref "D2") (pin "C") (pinfunction "C_C") (pintype "passive"))
      (node (ref "L3") (pin "P$1") (pinfunction "1_P$1") (pintype "passive"))
      (node (ref "U3") (pin "12") (pinfunction "P$12_12") (pintype "output"))
    )
    (net (code "41") (name "Net-(L4-1)") (class "Default")
      (node (ref "L4") (pin "P$1") (pinfunction "1_P$1") (pintype "passive"))
      (node (ref "U2") (pin "3") (pinfunction "P$3_3") (pintype "passive"))
    )
    (net (code "42") (name "Net-(L4-2)") (class "Default")
      (node (ref "D4") (pin "A") (pinfunction "A_A") (pintype "passive"))
      (node (ref "L4") (pin "P$2") (pinfunction "2_P$2") (pintype "passive"))
      (node (ref "U2") (pin "1") (pinfunction "P$1_1") (pintype "power_in"))
      (node (ref "U2") (pin "2") (pinfunction "P$2_2") (pintype "power_in"))
    )
    (net (code "43") (name "Net-(R40-2)") (class "Default")
      (node (ref "R40") (pin "P$2") (pinfunction "2_P$2") (pintype "passive"))
      (node (ref "X7") (pin "1") (pinfunction "P$1_1") (pintype "bidirectional"))
    )
    (net (code "44") (name "Net-(TR1-D)") (class "Default")
      (node (ref "R35") (pin "1") (pinfunction "1_1") (pintype "passive"))
      (node (ref "TR1") (pin "3") (pinfunction "D_3") (pintype "bidirectional"))
      (node (ref "U13") (pin "3") (pinfunction "P$3_3") (pintype "input"))
    )
    (net (code "45") (name "Net-(TR1-G)") (class "Default")
      (node (ref "R33") (pin "2") (pinfunction "2_2") (pintype "passive"))
      (node (ref "TR1") (pin "1") (pinfunction "G_1") (pintype "bidirectional"))
    )
    (net (code "46") (name "Net-(TR2-D)") (class "Default")
      (node (ref "R36") (pin "1") (pinfunction "1_1") (pintype "passive"))
      (node (ref "TR2") (pin "3") (pinfunction "D_3") (pintype "bidirectional"))
      (node (ref "U14") (pin "3") (pinfunction "P$3_3") (pintype "input"))
    )
    (net (code "47") (name "Net-(TR2-G)") (class "Default")
      (node (ref "R34") (pin "2") (pinfunction "2_2") (pintype "passive"))
      (node (ref "TR2") (pin "1") (pinfunction "G_1") (pintype "bidirectional"))
    )
    (net (code "48") (name "Net-(U1-P$6)") (class "Default")
      (node (ref "R1") (pin "2") (pinfunction "2_2") (pintype "passive"))
      (node (ref "U1") (pin "6") (pinfunction "P$6_6") (pintype "passive"))
    )
    (net (code "49") (name "Net-(U1-P$10)") (class "Default")
      (node (ref "C9") (pin "1") (pinfunction "1_1") (pintype "passive"))
      (node (ref "U1") (pin "10") (pinfunction "P$10_10") (pintype "input"))
      (node (ref "U1") (pin "9") (pinfunction "P$9_9") (pintype "output"))
    )
    (net (code "50") (name "Net-(U1-P$11)") (class "Default")
      (node (ref "C5") (pin "2") (pinfunction "2_2") (pintype "passive"))
      (node (ref "R3") (pin "1") (pinfunction "1_1") (pintype "passive"))
      (node (ref "R4") (pin "2") (pinfunction "2_2") (pintype "passive"))
      (node (ref "U1") (pin "11") (pinfunction "P$11_11") (pintype "input"))
    )
    (net (code "51") (name "Net-(U1-P$12)") (class "Default")
      (node (ref "R2") (pin "2") (pinfunction "2_2") (pintype "passive"))
      (node (ref "U1") (pin "12") (pinfunction "P$12_12") (pintype "input"))
    )
    (net (code "52") (name "Net-(U1-P$13)") (class "Default")
      (node (ref "C6") (pin "2") (pinfunction "2_2") (pintype "passive"))
      (node (ref "U1") (pin "13") (pinfunction "P$13_13") (pintype "input"))
    )
    (net (code "53") (name "Net-(U2-P$6)") (class "Default")
      (node (ref "R11") (pin "2") (pinfunction "2_2") (pintype "passive"))
      (node (ref "U2") (pin "6") (pinfunction "P$6_6") (pintype "passive"))
    )
    (net (code "54") (name "Net-(U2-P$10)") (class "Default")
      (node (ref "C21") (pin "1") (pinfunction "1_1") (pintype "passive"))
      (node (ref "U2") (pin "10") (pinfunction "P$10_10") (pintype "input"))
      (node (ref "U2") (pin "9") (pinfunction "P$9_9") (pintype "output"))
    )
    (net (code "55") (name "Net-(U2-P$11)") (class "Default")
      (node (ref "C17") (pin "2") (pinfunction "2_2") (pintype "passive"))
      (node (ref "R13") (pin "1") (pinfunction "1_1") (pintype "passive"))
      (node (ref "R14") (pin "2") (pinfunction "2_2") (pintype "passive"))
      (node (ref "U2") (pin "11") (pinfunction "P$11_11") (pintype "input"))
    )
    (net (code "56") (name "Net-(U2-P$12)") (class "Default")
      (node (ref "R12") (pin "2") (pinfunction "2_2") (pintype "passive"))
      (node (ref "U2") (pin "12") (pinfunction "P$12_12") (pintype "input"))
    )
    (net (code "57") (name "Net-(U2-P$13)") (class "Default")
      (node (ref "C18") (pin "2") (pinfunction "2_2") (pintype "passive"))
      (node (ref "U2") (pin "13") (pinfunction "P$13_13") (pintype "input"))
    )
    (net (code "58") (name "Net-(U3-P$2)") (class "Default")
      (node (ref "R7") (pin "1") (pinfunction "1_1") (pintype "passive"))
      (node (ref "R8") (pin "2") (pinfunction "2_2") (pintype "passive"))
      (node (ref "U3") (pin "2") (pinfunction "P$2_2") (pintype "input"))
    )
    (net (code "59") (name "Net-(U3-P$3)") (class "Default")
      (node (ref "R22") (pin "1") (pinfunction "1_1") (pintype "passive"))
      (node (ref "R23") (pin "2") (pinfunction "2_2") (pintype "passive"))
      (node (ref "U3") (pin "3") (pinfunction "P$3_3") (pintype "input"))
    )
    (net (code "60") (name "Net-(U3-P$6)") (class "Default")
      (node (ref "C11") (pin "1") (pinfunction "1_1") (pintype "passive"))
      (node (ref "U3") (pin "6") (pinfunction "P$6_6") (pintype "input"))
    )
    (net (code "61") (name "Net-(U3-P$7)") (class "Default")
      (node (ref "R5") (pin "1") (pinfunction "1_1") (pintype "passive"))
      (node (ref "R6") (pin "2") (pinfunction "2_2") (pintype "passive"))
      (node (ref "U3") (pin "7") (pinfunction "P$7_7") (pintype "input"))
    )
    (net (code "62") (name "Net-(U3-P$11)") (class "Default")
      (node (ref "C10") (pin "2") (pinfunction "2_2") (pintype "passive"))
      (node (ref "D3") (pin "C") (pinfunction "C_C") (pintype "passive"))
      (node (ref "U3") (pin "11") (pinfunction "P$11_11") (pintype "input"))
    )
    (net (code "63") (name "Net-(U6-P$3)") (class "Default")
      (node (ref "R24") (pin "2") (pinfunction "2_2") (pintype "passive"))
      (node (ref "U6") (pin "3") (pinfunction "P$3_3") (pintype "input"))
    )
    (net (code "64") (name "Net-(U6-P$6)") (class "Default")
      (node (ref "R25") (pin "2") (pinfunction "2_2") (pintype "passive"))
      (node (ref "R26") (pin "1") (pinfunction "1_1") (pintype "passive"))
      (node (ref "U6") (pin "6") (pinfunction "P$6_6") (pintype "input"))
    )
    (net (code "65") (name "Net-(U6-P$7)") (class "Default")
      (node (ref "R16") (pin "2") (pinfunction "2_2") (pintype "passive"))
      (node (ref "U6") (pin "7") (pinfunction "P$7_7") (pintype "input"))
    )
    (net (code "66") (name "Net-(U6-P$9)") (class "Default")
      (node (ref "R15") (pin "2") (pinfunction "2_2") (pintype "passive"))
      (node (ref "R16") (pin "1") (pinfunction "1_1") (pintype "passive"))
      (node (ref "U6") (pin "9") (pinfunction "P$9_9") (pintype "input"))
    )
    (net (code "67") (name "Net-(U7-EN)") (class "Default")
      (node (ref "R28") (pin "2") (pinfunction "2_2") (pintype "passive"))
      (node (ref "R29") (pin "1") (pinfunction "1_1") (pintype "passive"))
      (node (ref "U7") (pin "12") (pinfunction "EN_12") (pintype "input"))
    )
    (net (code "68") (name "Net-(U7-FB)") (class "Default")
      (node (ref "R17") (pin "1") (pinfunction "1_1") (pintype "passive"))
      (node (ref "R18") (pin "2") (pinfunction "2_2") (pintype "passive"))
      (node (ref "U7") (pin "3") (pinfunction "FB_3") (pintype "input"))
    )
    (net (code "69") (name "Net-(U7-L1)") (class "Default")
      (node (ref "L1") (pin "1") (pinfunction "1_1") (pintype "passive"))
      (node (ref "U7") (pin "8") (pinfunction "L1_8") (pintype "input"))
      (node (ref "U7") (pin "9") (pinfunction "L1_2_9") (pintype "input"))
    )
    (net (code "70") (name "Net-(U7-L2)") (class "Default")
      (node (ref "L1") (pin "2") (pinfunction "2_2") (pintype "passive"))
      (node (ref "U7") (pin "6") (pinfunction "L2_6") (pintype "input"))
      (node (ref "U7") (pin "7") (pinfunction "L2_2_7") (pintype "input"))
    )
    (net (code "71") (name "Net-(U7-SYNC{slash}PS)") (class "Default")
      (node (ref "C28") (pin "1") (pinfunction "1_1") (pintype "passive"))
      (node (ref "U7") (pin "1") (pinfunction "VINA_1") (pintype "bidirectional"))
      (node (ref "U7") (pin "13") (pinfunction "SYNC/PS_13") (pintype "input"))
    )
    (net (code "72") (name "Net-(U11-P$4)") (class "Default")
      (node (ref "R26") (pin "2") (pinfunction "2_2") (pintype "passive"))
      (node (ref "U11") (pin "4") (pinfunction "P$4_4") (pintype "bidirectional"))
    )
    (net (code "73") (name "Net-(U12-P$4)") (class "Default")
      (node (ref "R29") (pin "2") (pinfunction "2_2") (pintype "passive"))
      (node (ref "U12") (pin "4") (pinfunction "P$4_4") (pintype "bidirectional"))
    )
    (net (code "74") (name "Net-(U13-P$5)") (class "Default")
      (node (ref "R37") (pin "2") (pinfunction "2_2") (pintype "passive"))
      (node (ref "U13") (pin "5") (pinfunction "P$5_5") (pintype "passive"))
    )
    (net (code "75") (name "Net-(U14-P$5)") (class "Default")
      (node (ref "R38") (pin "2") (pinfunction "2_2") (pintype "passive"))
      (node (ref "U14") (pin "5") (pinfunction "P$5_5") (pintype "passive"))
    )
    (net (code "76") (name "Net-(X9-P$1)") (class "Default")
      (node (ref "D8") (pin "C") (pinfunction "C_C") (pintype "passive"))
      (node (ref "U8") (pin "P$5") (pinfunction "P$5_P$5") (pintype "power_in"))
      (node (ref "X9") (pin "1") (pinfunction "P$1_1") (pintype "bidirectional"))
    )
    (net (code "77") (name "Net-(X11-P$1)") (class "Default")
      (node (ref "JP1") (pin "1") (pinfunction "1_1") (pintype "passive"))
      (node (ref "X11") (pin "1") (pinfunction "P$1_1") (pintype "bidirectional"))
    )
    (net (code "78") (name "OBC_-FAULT") (class "Default")
      (node (ref "X1") (pin "34") (pinfunction "34_34") (pintype "bidirectional"))
    )
    (net (code "79") (name "OBC_OFF") (class "Default")
      (node (ref "X1") (pin "26") (pinfunction "26_26") (pintype "bidirectional"))
    )
    (net (code "80") (name "PANELTEMP_SCL") (class "Default")
      (node (ref "X1") (pin "29") (pinfunction "29_29") (pintype "bidirectional"))
      (node (ref "X2") (pin "2") (pinfunction "2_2") (pintype "passive"))
    )
    (net (code "81") (name "PANELTEMP_SDA") (class "Default")
      (node (ref "X1") (pin "31") (pinfunction "31_31") (pintype "bidirectional"))
      (node (ref "X2") (pin "1") (pinfunction "1_1") (pintype "passive"))
    )
    (net (code "82") (name "SCCHG_EN") (class "Default")
      (node (ref "U11") (pin "3") (pinfunction "P$3_3") (pintype "bidirectional"))
      (node (ref "X1") (pin "21") (pinfunction "21_21") (pintype "bidirectional"))
    )
    (net (code "83") (name "SCOUT_-PG") (class "Default")
      (node (ref "R31") (pin "2") (pinfunction "2_2") (pintype "passive"))
      (node (ref "U7") (pin "14") (pinfunction "PG_14") (pintype "output"))
      (node (ref "X1") (pin "50") (pinfunction "50_50") (pintype "bidirectional"))
    )
    (net (code "84") (name "SCOUT_EN") (class "Default")
      (node (ref "U12") (pin "3") (pinfunction "P$3_3") (pintype "bidirectional"))
      (node (ref "X1") (pin "22") (pinfunction "22_22") (pintype "bidirectional"))
    )
    (net (code "85") (name "SC_-ON") (class "Default")
      (node (ref "R30") (pin "1") (pinfunction "1_1") (pintype "passive"))
      (node (ref "U8") (pin "P$4") (pinfunction "P$4_P$4") (pintype "output"))
      (node (ref "X1") (pin "40") (pinfunction "40_40") (pintype "bidirectional"))
    )
    (net (code "86") (name "SC_-PFO") (class "Default")
      (node (ref "R32") (pin "2") (pinfunction "2_2") (pintype "passive"))
      (node (ref "U6") (pin "8") (pinfunction "P$8_8") (pintype "output"))
      (node (ref "X1") (pin "48") (pinfunction "48_48") (pintype "bidirectional"))
    )
    (net (code "87") (name "SECONDARY_SCL") (class "Default")
      (node (ref "X1") (pin "47") (pinfunction "47_47") (pintype "bidirectional"))
      (node (ref "X4") (pin "7") (pinfunction "7_7") (pintype "passive"))
    )
    (net (code "88") (name "SECONDARY_SDA") (class "Default")
      (node (ref "X1") (pin "49") (pinfunction "49_49") (pintype "bidirectional"))
      (node (ref "X4") (pin "6") (pinfunction "6_6") (pintype "passive"))
    )
    (net (code "89") (name "SENSE") (class "Default")
      (node (ref "L3") (pin "P$2") (pinfunction "2_P$2") (pintype "passive"))
      (node (ref "R9") (pin "P$1") (pinfunction "1_P$1") (pintype "passive"))
      (node (ref "U3") (pin "10") (pinfunction "P$10_10") (pintype "input"))
    )
    (net (code "90") (name "SOLAR_-ON") (class "Default")
      (node (ref "R21") (pin "1") (pinfunction "1_1") (pintype "passive"))
      (node (ref "U4") (pin "P$4") (pinfunction "P$4_P$4") (pintype "output"))
      (node (ref "X1") (pin "36") (pinfunction "36_36") (pintype "bidirectional"))
    )
    (net (code "91") (name "SOLAR_CS1") (class "Default")
      (node (ref "X1") (pin "15") (pinfunction "15_15") (pintype "bidirectional"))
      (node (ref "X2") (pin "8") (pinfunction "8_8") (pintype "passive"))
    )
    (net (code "92") (name "SOLAR_CS2") (class "Default")
      (node (ref "X1") (pin "14") (pinfunction "14_14") (pintype "bidirectional"))
      (node (ref "X2") (pin "7") (pinfunction "7_7") (pintype "passive"))
    )
    (net (code "93") (name "SOLAR_CS3") (class "Default")
      (node (ref "X1") (pin "17") (pinfunction "17_17") (pintype "bidirectional"))
      (node (ref "X2") (pin "6") (pinfunction "6_6") (pintype "passive"))
    )
    (net (code "94") (name "SOLAR_CS4") (class "Default")
      (node (ref "X1") (pin "16") (pinfunction "16_16") (pintype "bidirectional"))
      (node (ref "X2") (pin "5") (pinfunction "5_5") (pintype "passive"))
    )
    (net (code "95") (name "SOLAR_CS5") (class "Default")
      (node (ref "X1") (pin "18") (pinfunction "18_18") (pintype "bidirectional"))
      (node (ref "X2") (pin "4") (pinfunction "4_4") (pintype "passive"))
    )
    (net (code "96") (name "STRUT_GND") (class "Default")
      (node (ref "C36") (pin "1") (pinfunction "1_1") (pintype "passive"))
      (node (ref "H4") (pin "B3,2") (pinfunction "MOUNT_B3,2") (pintype "passive"))
      (node (ref "R39") (pin "2") (pinfunction "2_2") (pintype "passive"))
    )
    (net (code "97") (name "SUN") (class "Default")
      (node (ref "X1") (pin "27") (pinfunction "27_27") (pintype "bidirectional"))
      (node (ref "X16") (pin "1") (pinfunction "P$1_1") (pintype "bidirectional"))
    )
    (net (code "98") (name "VBAT") (class "Default")
      (node (ref "C3") (pin "P$1") (pinfunction "1_P$1") (pintype "passive"))
      (node (ref "C35") (pin "1") (pinfunction "1_1") (pintype "passive"))
      (node (ref "C4") (pin "P$1") (pinfunction "1_P$1") (pintype "passive"))
      (node (ref "D3") (pin "A") (pinfunction "A_A") (pintype "passive"))
      (node (ref "JP10") (pin "1") (pinfunction "1_1") (pintype "passive"))
      (node (ref "JP4") (pin "2") (pinfunction "2_2") (pintype "passive"))
      (node (ref "R35") (pin "2") (pinfunction "2_2") (pintype "passive"))
      (node (ref "R36") (pin "2") (pinfunction "2_2") (pintype "passive"))
      (node (ref "R5") (pin "2") (pinfunction "2_2") (pintype "passive"))
      (node (ref "R9") (pin "P$2") (pinfunction "2_P$2") (pintype "passive"))
      (node (ref "U13") (pin "1") (pinfunction "P$1_1") (pintype "input"))
      (node (ref "U13") (pin "2") (pinfunction "P$2_2") (pintype "input"))
      (node (ref "U14") (pin "1") (pinfunction "P$1_1") (pintype "input"))
      (node (ref "U14") (pin "2") (pinfunction "P$2_2") (pintype "input"))
      (node (ref "U3") (pin "9") (pinfunction "P$9_9") (pintype "input"))
      (node (ref "X1") (pin "11") (pinfunction "11_11") (pintype "bidirectional"))
      (node (ref "X1") (pin "12") (pinfunction "12_12") (pintype "bidirectional"))
      (node (ref "X13") (pin "1") (pinfunction "P$1_1") (pintype "bidirectional"))
      (node (ref "X14") (pin "1") (pinfunction "P$1_1") (pintype "bidirectional"))
    )
    (net (code "99") (name "VBUS") (class "Default")
      (node (ref "C12") (pin "1") (pinfunction "+_1") (pintype "passive"))
      (node (ref "C13") (pin "1") (pinfunction "+_1") (pintype "passive"))
      (node (ref "C14") (pin "1") (pinfunction "+_1") (pintype "passive"))
      (node (ref "JP9") (pin "1") (pinfunction "1_1") (pintype "passive"))
      (node (ref "R19") (pin "2") (pinfunction "2_2") (pintype "passive"))
      (node (ref "R20") (pin "2") (pinfunction "2_2") (pintype "passive"))
      (node (ref "R21") (pin "2") (pinfunction "2_2") (pintype "passive"))
      (node (ref "R27") (pin "2") (pinfunction "2_2") (pintype "passive"))
      (node (ref "R30") (pin "2") (pinfunction "2_2") (pintype "passive"))
      (node (ref "R31") (pin "1") (pinfunction "1_1") (pintype "passive"))
      (node (ref "R32") (pin "1") (pinfunction "1_1") (pintype "passive"))
      (node (ref "X1") (pin "10") (pinfunction "10_10") (pintype "bidirectional"))
      (node (ref "X1") (pin "7") (pinfunction "7_7") (pintype "bidirectional"))
      (node (ref "X1") (pin "8") (pinfunction "8_8") (pintype "bidirectional"))
      (node (ref "X1") (pin "9") (pinfunction "9_9") (pintype "bidirectional"))
      (node (ref "X15") (pin "1") (pinfunction "P$1_1") (pintype "bidirectional"))
      (node (ref "X4") (pin "1") (pinfunction "1_1") (pintype "passive"))
      (node (ref "X4") (pin "2") (pinfunction "2_2") (pintype "passive"))
    )
    (net (code "100") (name "VMID") (class "Default")
      (node (ref "JP11") (pin "2") (pinfunction "2_2") (pintype "passive"))
      (node (ref "U6") (pin "10") (pinfunction "P$10_10") (pintype "power_in"))
    )
    (net (code "101") (name "VSC_IN") (class "Default")
      (node (ref "C16") (pin "P$1") (pinfunction "1_P$1") (pintype "passive"))
      (node (ref "C17") (pin "1") (pinfunction "1_1") (pintype "passive"))
      (node (ref "C20") (pin "1") (pinfunction "1_1") (pintype "passive"))
      (node (ref "C22") (pin "P$1") (pinfunction "1_P$1") (pintype "passive"))
      (node (ref "D4") (pin "C") (pinfunction "C_C") (pintype "passive"))
      (node (ref "R13") (pin "2") (pinfunction "2_2") (pintype "passive"))
      (node (ref "R15") (pin "1") (pinfunction "1_1") (pintype "passive"))
      (node (ref "R25") (pin "1") (pinfunction "1_1") (pintype "passive"))
      (node (ref "U11") (pin "6") (pinfunction "P$6_6") (pintype "bidirectional"))
      (node (ref "U6") (pin "11") (pinfunction "P$11_11") (pintype "power_in"))
      (node (ref "U6") (pin "12") (pinfunction "P$12_12") (pintype "power_in"))
      (node (ref "U6") (pin "5") (pinfunction "P$5_5") (pintype "input"))
    )
    (net (code "102") (name "VSOLAR") (class "Default")
      (node (ref "JP6") (pin "2") (pinfunction "2_2") (pintype "passive"))
      (node (ref "X1") (pin "5") (pinfunction "5_5") (pintype "bidirectional"))
      (node (ref "X1") (pin "6") (pinfunction "6_6") (pintype "bidirectional"))
      (node (ref "X3") (pin "6") (pinfunction "6_6") (pintype "passive"))
      (node (ref "X3") (pin "7") (pinfunction "7_7") (pintype "passive"))
      (node (ref "X3") (pin "8") (pinfunction "8_8") (pintype "passive"))
    )
    (net (code "103") (name "VSUPERCAP") (class "Default")
      (node (ref "C23") (pin "P$1") (pinfunction "1_P$1") (pintype "passive"))
      (node (ref "C24") (pin "P$1") (pinfunction "1_P$1") (pintype "passive"))
      (node (ref "JP11") (pin "1") (pinfunction "1_1") (pintype "passive"))
      (node (ref "R28") (pin "1") (pinfunction "1_1") (pintype "passive"))
      (node (ref "U12") (pin "6") (pinfunction "P$6_6") (pintype "bidirectional"))
      (node (ref "U6") (pin "1") (pinfunction "P$1_1") (pintype "power_in"))
      (node (ref "U6") (pin "2") (pinfunction "P$2_2") (pintype "power_in"))
      (node (ref "U7") (pin "10") (pinfunction "VIN_10") (pintype "input"))
      (node (ref "U7") (pin "11") (pinfunction "VIN2_11") (pintype "input"))
      (node (ref "X1") (pin "13") (pinfunction "13_13") (pintype "bidirectional"))
    )
    (net (code "104") (name "unconnected-(H1-MOUNT-PadB3,2)") (class "Default")
      (node (ref "H1") (pin "B3,2") (pinfunction "MOUNT_B3,2") (pintype "passive"))
    )
    (net (code "105") (name "unconnected-(H2-MOUNT-PadB3,2)") (class "Default")
      (node (ref "H2") (pin "B3,2") (pinfunction "MOUNT_B3,2") (pintype "passive"))
    )
    (net (code "106") (name "unconnected-(H3-MOUNT-PadB3,2)") (class "Default")
      (node (ref "H3") (pin "B3,2") (pinfunction "MOUNT_B3,2") (pintype "passive"))
    )
    (net (code "107") (name "unconnected-(U3-P$8-Pad8)") (class "Default")
      (node (ref "U3") (pin "8") (pinfunction "P$8_8") (pintype "input"))
    )
    (net (code "108") (name "unconnected-(U6-P$4-Pad4)") (class "Default")
      (node (ref "U6") (pin "4") (pinfunction "P$4_4") (pintype "input"))
    )
    (net (code "109") (name "unconnected-(U9-PadP$4)") (class "Default")
      (node (ref "U9") (pin "P$4") (pinfunction "P$4_P$4") (pintype "output"))
    )
    (net (code "110") (name "unconnected-(U10-PadP$4)") (class "Default")
      (node (ref "U10") (pin "P$4") (pinfunction "P$4_P$4") (pintype "output"))
    )
    (net (code "111") (name "unconnected-(X1-Pad3)") (class "Default")
      (node (ref "X1") (pin "3") (pinfunction "3_3") (pintype "bidirectional"))
    )
    (net (code "112") (name "unconnected-(X1-Pad4)") (class "Default")
      (node (ref "X1") (pin "4") (pinfunction "4_4") (pintype "bidirectional"))
    )
    (net (code "113") (name "unconnected-(X8-PadC)") (class "Default")
      (node (ref "X8") (pin "C") (pinfunction "C_C") (pintype "bidirectional"))
    )
    (net (code "114") (name "unconnected-(X8-PadNC)") (class "Default")
      (node (ref "X8") (pin "NC") (pinfunction "NC_NC") (pintype "bidirectional"))
    )
    (net (code "115") (name "unconnected-(X8-PadNO)") (class "Default")
      (node (ref "X8") (pin "NO") (pinfunction "NO_NO") (pintype "bidirectional"))
    )
  )
)
